# band_pass_filter.net
KiCad netlist of a schematic drawn in EAGLE
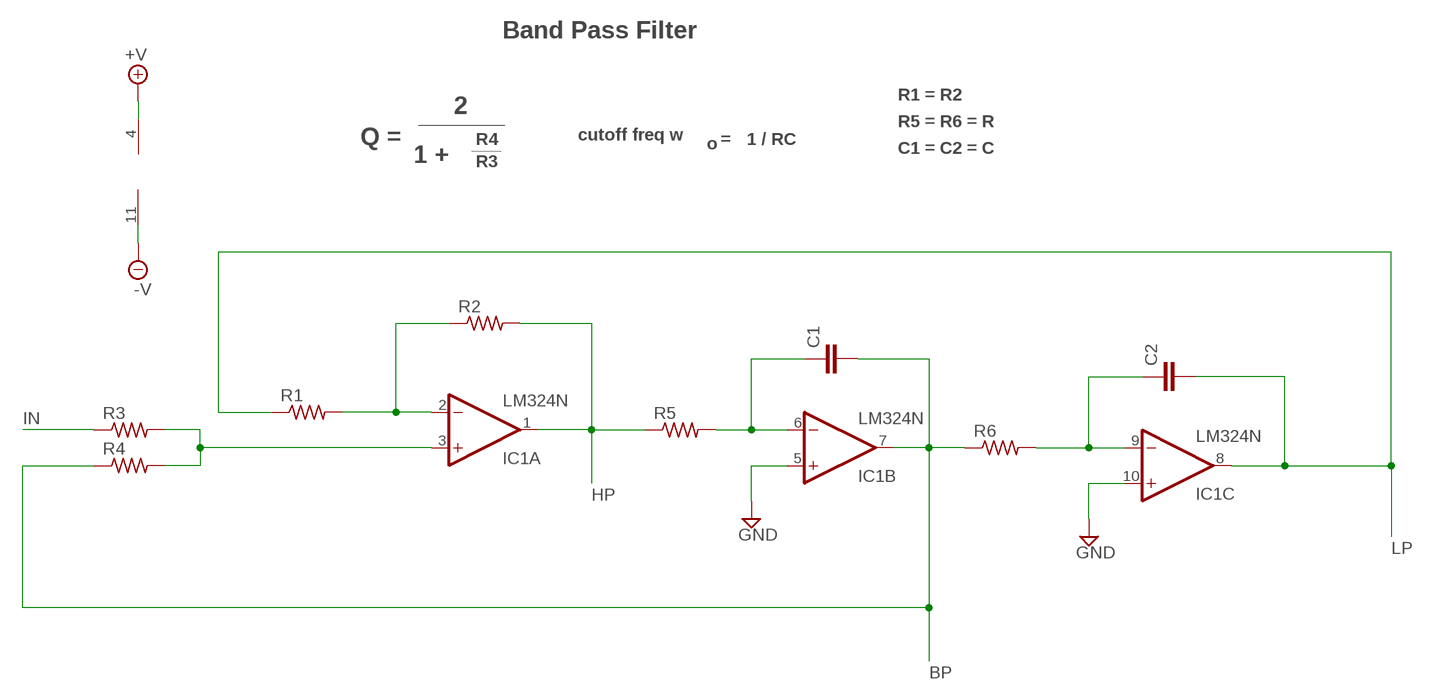
[diagram p0: schematic, sheet 1]

(export (version "E")
  (design (tool "Eeschema 10.0.6"))
  (components
    (comp (ref "C1")
      (value "CERAMIC_CAPACITOR")
      (footprint "eagle-import:CERAMIC_CAP")
      (libsource (lib "eagle-import") (part "CERAMIC_CAPACITOR"))
    )
    (comp (ref "C2")
      (value "CERAMIC_CAPACITOR")
      (footprint "eagle-import:CERAMIC_CAP")
      (libsource (lib "eagle-import") (part "CERAMIC_CAPACITOR"))
    )
    (comp (ref "IC1")
      (value "LM324N")
      (footprint "eagle-import:DIL14")
      (libsource (lib "eagle-import") (part "LM324N"))
    )
    (comp (ref "R1")
      (value "RESISTOR")
      (footprint "eagle-import:RESISTOR")
      (libsource (lib "eagle-import") (part "RESISTOR"))
    )
    (comp (ref "R2")
      (value "RESISTOR")
      (footprint "eagle-import:RESISTOR")
      (libsource (lib "eagle-import") (part "RESISTOR"))
    )
    (comp (ref "R3")
      (value "RESISTOR")
      (footprint "eagle-import:RESISTOR")
      (libsource (lib "eagle-import") (part "RESISTOR"))
    )
    (comp (ref "R4")
      (value "RESISTOR")
      (footprint "eagle-import:RESISTOR")
      (libsource (lib "eagle-import") (part "RESISTOR"))
    )
    (comp (ref "R5")
      (value "RESISTOR")
      (footprint "eagle-import:RESISTOR")
      (libsource (lib "eagle-import") (part "RESISTOR"))
    )
    (comp (ref "R6")
      (value "RESISTOR")
      (footprint "eagle-import:RESISTOR")
      (libsource (lib "eagle-import") (part "RESISTOR"))
    )
  )
  (nets
    (net (code "1") (name "+V") (class "Default")
      (node (ref "IC1") (pin "4") (pinfunction "V+_4") (pintype "power_in"))
    )
    (net (code "2") (name "-V") (class "Default")
      (node (ref "IC1") (pin "11") (pinfunction "V-_11") (pintype "power_in"))
    )
    (net (code "3") (name "/BP") (class "Default")
      (node (ref "C1") (pin "2") (pinfunction "2_2") (pintype "passive"))
      (node (ref "IC1") (pin "7") (pinfunction "OUT_7") (pintype "output"))
      (node (ref "R4") (pin "1") (pinfunction "1_1") (pintype "passive"))
      (node (ref "R6") (pin "1") (pinfunction "1_1") (pintype "passive"))
    )
    (net (code "4") (name "/HP") (class "Default")
      (node (ref "IC1") (pin "1") (pinfunction "OUT_1") (pintype "output"))
      (node (ref "R2") (pin "2") (pinfunction "2_2") (pintype "passive"))
      (node (ref "R5") (pin "1") (pinfunction "1_1") (pintype "passive"))
    )
    (net (code "5") (name "/IN") (class "Default")
      (node (ref "R3") (pin "1") (pinfunction "1_1") (pintype "passive"))
    )
    (net (code "6") (name "/LP") (class "Default")
      (node (ref "C2") (pin "2") (pinfunction "2_2") (pintype "passive"))
      (node (ref "IC1") (pin "8") (pinfunction "OUT_8") (pintype "output"))
      (node (ref "R1") (pin "1") (pinfunction "1_1") (pintype "passive"))
    )
    (net (code "7") (name "GND") (class "Default")
      (node (ref "IC1") (pin "10") (pinfunction "+IN_10") (pintype "input"))
      (node (ref "IC1") (pin "5") (pinfunction "+IN_5") (pintype "input"))
    )
    (net (code "8") (name "Net-(IC1A-+IN)") (class "Default")
      (node (ref "IC1") (pin "3") (pinfunction "+IN_3") (pintype "input"))
      (node (ref "R3") (pin "2") (pinfunction "2_2") (pintype "passive"))
      (node (ref "R4") (pin "2") (pinfunction "2_2") (pintype "passive"))
    )
    (net (code "9") (name "Net-(IC1A--IN)") (class "Default")
      (node (ref "IC1") (pin "2") (pinfunction "-IN_2") (pintype "input"))
      (node (ref "R1") (pin "2") (pinfunction "2_2") (pintype "passive"))
      (node (ref "R2") (pin "1") (pinfunction "1_1") (pintype "passive"))
    )
    (net (code "10") (name "Net-(IC1B--IN)") (class "Default")
      (node (ref "C1") (pin "1") (pinfunction "1_1") (pintype "passive"))
      (node (ref "IC1") (pin "6") (pinfunction "-IN_6") (pintype "input"))
      (node (ref "R5") (pin "2") (pinfunction "2_2") (pintype "passive"))
    )
    (net (code "11") (name "Net-(IC1C--IN)") (class "Default")
      (node (ref "C2") (pin "1") (pinfunction "1_1") (pintype "passive"))
      (node (ref "IC1") (pin "9") (pinfunction "-IN_9") (pintype "input"))
      (node (ref "R6") (pin "2") (pinfunction "2_2") (pintype "passive"))
    )
  )
)
